# Fri3D_2026_Peripherals.net
KiCad netlist of a schematic drawn in Altium Designer
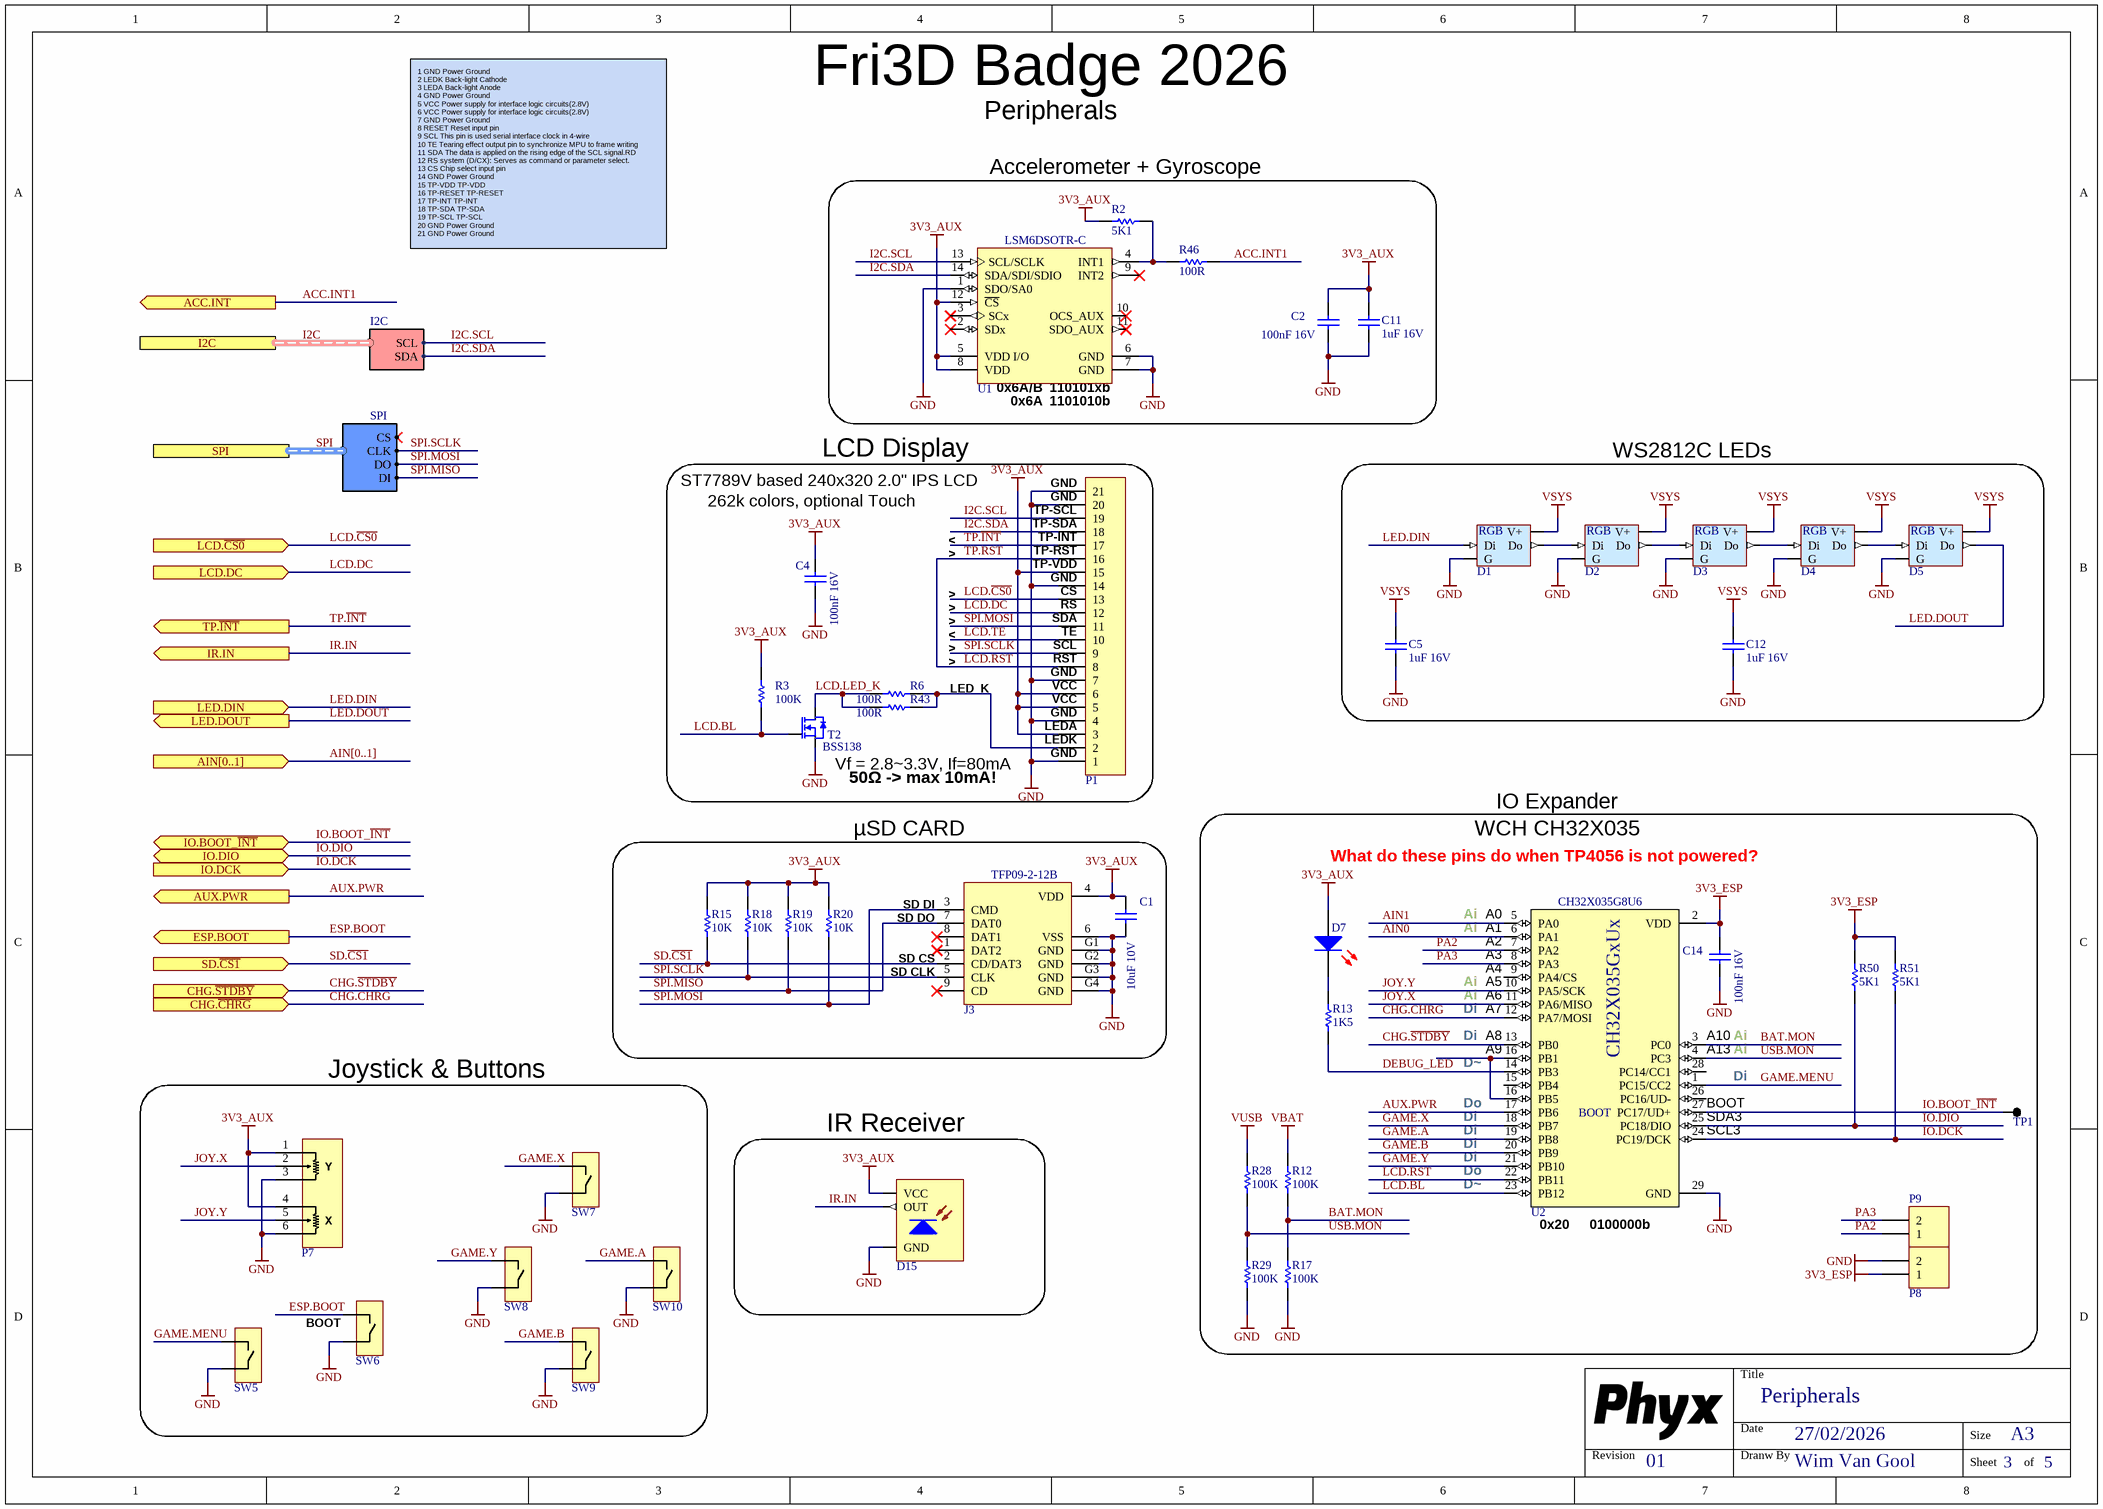
[diagram p0: Fri3D_2026_Peripherals.SchDoc]

(export (version "E")
  (design (tool "Eeschema 10.0.6"))
  (components
    (comp (ref "C1")
      (value "10uF 10V")
      (footprint "C0805_N")
      (description "Capacitor Ceramic")
      (libsource (lib "Phyx_Components") (part "CAP_CERAMIC"))
    )
    (comp (ref "C2")
      (value "100nF 16V")
      (footprint "C0603_N")
      (description "Capacitor Ceramic")
      (libsource (lib "Phyx_Components") (part "CAP_CERAMIC"))
    )
    (comp (ref "C4")
      (value "100nF 16V")
      (footprint "C0603_N")
      (description "Capacitor Ceramic")
      (libsource (lib "Phyx_Components") (part "CAP_CERAMIC"))
    )
    (comp (ref "C5")
      (value "1uF 16V")
      (footprint "C0603_N")
      (description "Capacitor Ceramic")
      (libsource (lib "Phyx_Components") (part "CAP_CERAMIC"))
    )
    (comp (ref "C11")
      (value "1uF 16V")
      (footprint "C0603_N")
      (description "Capacitor Ceramic")
      (libsource (lib "Phyx_Components") (part "CAP_CERAMIC"))
    )
    (comp (ref "C12")
      (value "1uF 16V")
      (footprint "C0603_N")
      (description "Capacitor Ceramic")
      (libsource (lib "Phyx_Components") (part "CAP_CERAMIC"))
    )
    (comp (ref "C14")
      (value "100nF 16V")
      (footprint "C0603_N")
      (description "Capacitor Ceramic")
      (libsource (lib "Phyx_Components") (part "CAP_CERAMIC"))
    )
    (comp (ref "D1")
      (value "WS2812 based digital RGB LED 5050 White package reduced current")
      (footprint "LED_5050_WS2812B_WHITE")
      (description "=Description")
      (libsource (lib "Phyx_Components") (part "LED_RGB_WS2812B_5050"))
    )
    (comp (ref "D2")
      (value "WS2812 based digital RGB LED 5050 White package reduced current")
      (footprint "LED_5050_WS2812B_WHITE")
      (description "=Description")
      (libsource (lib "Phyx_Components") (part "LED_RGB_WS2812B_5050"))
    )
    (comp (ref "D3")
      (value "WS2812 based digital RGB LED 5050 White package reduced current")
      (footprint "LED_5050_WS2812B_WHITE")
      (description "=Description")
      (libsource (lib "Phyx_Components") (part "LED_RGB_WS2812B_5050"))
    )
    (comp (ref "D4")
      (value "WS2812 based digital RGB LED 5050 White package reduced current")
      (footprint "LED_5050_WS2812B_WHITE")
      (description "=Description")
      (libsource (lib "Phyx_Components") (part "LED_RGB_WS2812B_5050"))
    )
    (comp (ref "D5")
      (value "WS2812 based digital RGB LED 5050 White package reduced current")
      (footprint "LED_5050_WS2812B_WHITE")
      (description "=Description")
      (libsource (lib "Phyx_Components") (part "LED_RGB_WS2812B_5050"))
    )
    (comp (ref "D7")
      (value "Default 0805 Red LED")
      (footprint "LED_0805_RD")
      (description "=Description")
      (libsource (lib "Phyx_Components") (part "LED_RED"))
    )
    (comp (ref "D15")
      (value "ZIRM-5042B-42-Z2 Infrared Receiver 38 kHz 45° 2.7-5.5V 940nm")
      (footprint "CHAU_ZIRM-5042B-42-Z2")
      (description "=Description")
      (libsource (lib "Phyx_Components") (part "PHO_IR_TSOP381x"))
    )
    (comp (ref "J3")
      (value "Micro SD PiPo Push-Push")
      (footprint "TFP09-2-12B")
      (description "=Description")
      (fields (field (name "SUPPLIER PART NUMBER 1") "TFP09-2-12B"))
      (libsource (lib "Phyx_Components") (part "TFP09-2-12B"))
    )
    (comp (ref "P1")
      (value "FH35C-21S-0.3SHW Top and Bottom Contacts 0.3mm 21pin")
      (footprint "HRS_FH35C-21S-0.3SHW")
      (libsource (lib "Phyx_Components") (part "Header 21"))
    )
    (comp (ref "P7")
      (value "PSP Mini Joystick")
      (footprint "PSP_Mini_Joystick")
      (libsource (lib "Phyx_Components") (part "PSP_Mini_Joystick"))
    )
    (comp (ref "P8")
      (value "Header 2")
      (footprint "HDR1X2")
      (libsource (lib "Phyx_Components") (part "Header 2"))
    )
    (comp (ref "P9")
      (value "Header 2")
      (footprint "HDR1X2")
      (libsource (lib "Phyx_Components") (part "Header 2"))
    )
    (comp (ref "R2")
      (value "5K1")
      (footprint "R0603_N")
      (libsource (lib "Phyx_Components") (part "RESISTOR"))
    )
    (comp (ref "R3")
      (value "100K")
      (footprint "R0603_N")
      (libsource (lib "Phyx_Components") (part "RESISTOR"))
    )
    (comp (ref "R6")
      (value "100R")
      (footprint "R0603_N")
      (libsource (lib "Phyx_Components") (part "RESISTOR"))
    )
    (comp (ref "R12")
      (value "100K")
      (footprint "R0603_N")
      (libsource (lib "Phyx_Components") (part "RESISTOR"))
    )
    (comp (ref "R13")
      (value "1K5")
      (footprint "R0603_N")
      (libsource (lib "Phyx_Components") (part "RESISTOR"))
    )
    (comp (ref "R15")
      (value "10K")
      (footprint "R0603_N")
      (libsource (lib "Phyx_Components") (part "RESISTOR"))
    )
    (comp (ref "R17")
      (value "100K")
      (footprint "R0603_N")
      (libsource (lib "Phyx_Components") (part "RESISTOR"))
    )
    (comp (ref "R18")
      (value "10K")
      (footprint "R0603_N")
      (libsource (lib "Phyx_Components") (part "RESISTOR"))
    )
    (comp (ref "R19")
      (value "10K")
      (footprint "R0603_N")
      (libsource (lib "Phyx_Components") (part "RESISTOR"))
    )
    (comp (ref "R20")
      (value "10K")
      (footprint "R0603_N")
      (libsource (lib "Phyx_Components") (part "RESISTOR"))
    )
    (comp (ref "R28")
      (value "100K")
      (footprint "R0603_N")
      (libsource (lib "Phyx_Components") (part "RESISTOR"))
    )
    (comp (ref "R29")
      (value "100K")
      (footprint "R0603_N")
      (libsource (lib "Phyx_Components") (part "RESISTOR"))
    )
    (comp (ref "R43")
      (value "100R")
      (footprint "R0603_N")
      (libsource (lib "Phyx_Components") (part "RESISTOR"))
    )
    (comp (ref "R46")
      (value "100R")
      (footprint "R0603_N")
      (libsource (lib "Phyx_Components") (part "RESISTOR"))
    )
    (comp (ref "R50")
      (value "5K1")
      (footprint "R0603_N")
      (libsource (lib "Phyx_Components") (part "RESISTOR"))
    )
    (comp (ref "R51")
      (value "5K1")
      (footprint "R0603_N")
      (libsource (lib "Phyx_Components") (part "RESISTOR"))
    )
    (comp (ref "SW5")
      (value "SKPMAME010 6x6 TACTG Switch")
      (footprint "ALPS_SKPMAME010")
      (libsource (lib "Phyx_Components") (part "SW_TACT"))
    )
    (comp (ref "SW6")
      (value "SKPMAME010 6x6 TACTG Switch")
      (footprint "ALPS_SKPMAME010")
      (libsource (lib "Phyx_Components") (part "SW_TACT"))
    )
    (comp (ref "SW7")
      (value "SKPMAME010 6x6 TACTG Switch")
      (footprint "ALPS_SKPMAME010")
      (libsource (lib "Phyx_Components") (part "SW_TACT"))
    )
    (comp (ref "SW8")
      (value "SKPMAME010 6x6 TACTG Switch")
      (footprint "ALPS_SKPMAME010")
      (libsource (lib "Phyx_Components") (part "SW_TACT"))
    )
    (comp (ref "SW9")
      (value "SKPMAME010 6x6 TACTG Switch")
      (footprint "ALPS_SKPMAME010")
      (libsource (lib "Phyx_Components") (part "SW_TACT"))
    )
    (comp (ref "SW10")
      (value "SKPMAME010 6x6 TACTG Switch")
      (footprint "ALPS_SKPMAME010")
      (libsource (lib "Phyx_Components") (part "SW_TACT"))
    )
    (comp (ref "T2")
      (value "BSS138")
      (footprint "SOT23-3")
      (fields (field (name "Comment") "0.2A N-Ch MOSFET Vgs 3.2"))
      (libsource (lib "Phyx_Components") (part "N_MOSFET_GSD"))
    )
    (comp (ref "TP1")
      (value "TEST_PAD")
      (footprint "TP_1.5mm_0.9mm")
      (libsource (lib "Phyx_Components") (part "TEST_PAD"))
    )
    (comp (ref "U1")
      (value "LSM6DSOTR-C")
      (footprint "STM_LGA14_2.5x3")
      (description "ACCELERO GYRO # LSM6DSOTR-C")
      (fields (field (name "Comment") "Acceleration ±2, ±4, ±8, ±16g Gyro ±125, ±250, ±500, ±1000, ±2000dps"))
      (libsource (lib "Phyx_Components") (part "STM_LSM6DSO"))
    )
    (comp (ref "U2")
      (value "CH32X035G8U6")
      (footprint "QFN_28_4.0x4.0_P0.4")
      (fields
        (field (name "Comment") "WCH CH32X035G8U6 QFN28 RISC-V 32-bit MCU, 62KB Flash, 10KB RAM, USB PD")
      )
      (libsource (lib "Phyx_Components") (part "WCH_CH32X035GxUx"))
    )
  )
  (nets
    (net (code "3") (name "/ACC.INT1") (class "Default")
      (node (ref "R46") (pin "2") (pinfunction "2_2") (pintype "passive"))
    )
    (net (code "4") (name "/AIN0") (class "Default")
      (node (ref "U2") (pin "6") (pinfunction "PA1_6") (pintype "bidirectional"))
    )
    (net (code "5") (name "/AIN1") (class "Default")
      (node (ref "U2") (pin "5") (pinfunction "PA0_5") (pintype "bidirectional"))
    )
    (net (code "7") (name "/AUX.PWR") (class "Default")
      (node (ref "U2") (pin "17") (pinfunction "PB6_17") (pintype "bidirectional"))
    )
    (net (code "8") (name "/BAT.MON") (class "Default")
      (node (ref "R12") (pin "2") (pinfunction "2_2") (pintype "passive"))
      (node (ref "R17") (pin "1") (pinfunction "1_1") (pintype "passive"))
      (node (ref "U2") (pin "3") (pinfunction "PC0_3") (pintype "bidirectional"))
    )
    (net (code "9") (name "/CHG.~{CHRG}") (class "Default")
      (node (ref "U2") (pin "12") (pinfunction "PA7/MOSI_12") (pintype "bidirectional"))
    )
    (net (code "10") (name "/CHG.~{STDBY}") (class "Default")
      (node (ref "U2") (pin "13") (pinfunction "PB0_13") (pintype "bidirectional"))
    )
    (net (code "11") (name "/DEBUG_LED") (class "Default")
      (node (ref "R13") (pin "2") (pinfunction "2_2") (pintype "passive"))
      (node (ref "U2") (pin "14") (pinfunction "PB3_14") (pintype "bidirectional"))
    )
    (net (code "12") (name "/ESP.BOOT") (class "Default")
      (node (ref "SW6") (pin "1") (pinfunction "1_1") (pintype "passive"))
    )
    (net (code "13") (name "/GAME.A") (class "Default")
      (node (ref "SW10") (pin "1") (pinfunction "1_1") (pintype "passive"))
      (node (ref "U2") (pin "19") (pinfunction "PB8_19") (pintype "bidirectional"))
    )
    (net (code "14") (name "/GAME.B") (class "Default")
      (node (ref "SW9") (pin "1") (pinfunction "1_1") (pintype "passive"))
      (node (ref "U2") (pin "20") (pinfunction "PB9_20") (pintype "bidirectional"))
    )
    (net (code "15") (name "/GAME.MENU") (class "Default")
      (node (ref "SW5") (pin "1") (pinfunction "1_1") (pintype "passive"))
      (node (ref "U2") (pin "1") (pinfunction "PC15/CC2_1") (pintype "bidirectional"))
    )
    (net (code "16") (name "/GAME.X") (class "Default")
      (node (ref "SW7") (pin "1") (pinfunction "1_1") (pintype "passive"))
      (node (ref "U2") (pin "18") (pinfunction "PB7_18") (pintype "bidirectional"))
    )
    (net (code "17") (name "/GAME.Y") (class "Default")
      (node (ref "SW8") (pin "1") (pinfunction "1_1") (pintype "passive"))
      (node (ref "U2") (pin "21") (pinfunction "PB10_21") (pintype "bidirectional"))
    )
    (net (code "18") (name "/I2C.SCL") (class "Default")
      (node (ref "P1") (pin "19") (pinfunction "19_19") (pintype "passive"))
      (node (ref "U1") (pin "13") (pinfunction "SCL/SCLK_13") (pintype "input"))
    )
    (net (code "19") (name "/I2C.SDA") (class "Default")
      (node (ref "P1") (pin "18") (pinfunction "18_18") (pintype "passive"))
      (node (ref "U1") (pin "14") (pinfunction "SDA/SDI/SDIO_14") (pintype "bidirectional"))
    )
    (net (code "21") (name "/IO.BOOT_~{INT}") (class "Default")
      (node (ref "TP1") (pin "1") (pinfunction "1_1") (pintype "passive"))
      (node (ref "U2") (pin "27") (pinfunction "PC17/UD+_27") (pintype "bidirectional"))
    )
    (net (code "22") (name "/IO.DCK") (class "Default")
      (node (ref "R51") (pin "2") (pinfunction "2_2") (pintype "passive"))
      (node (ref "U2") (pin "24") (pinfunction "PC19/DCK_24") (pintype "bidirectional"))
    )
    (net (code "23") (name "/IO.DIO") (class "Default")
      (node (ref "R50") (pin "2") (pinfunction "2_2") (pintype "passive"))
      (node (ref "U2") (pin "25") (pinfunction "PC18/DIO_25") (pintype "bidirectional"))
    )
    (net (code "24") (name "/IR.IN") (class "Default")
      (node (ref "D15") (pin "1") (pinfunction "OUT_1") (pintype "output"))
    )
    (net (code "25") (name "/JOY.X") (class "Default")
      (node (ref "P7") (pin "2") (pinfunction "2_2") (pintype "passive"))
      (node (ref "U2") (pin "11") (pinfunction "PA6/MISO_11") (pintype "bidirectional"))
    )
    (net (code "26") (name "/JOY.Y") (class "Default")
      (node (ref "P7") (pin "5") (pinfunction "5_5") (pintype "passive"))
      (node (ref "U2") (pin "10") (pinfunction "PA5/SCK_10") (pintype "bidirectional"))
    )
    (net (code "27") (name "/LCD.BL") (class "Default")
      (node (ref "R3") (pin "2") (pinfunction "2_2") (pintype "passive"))
      (node (ref "T2") (pin "1") (pinfunction "G_1") (pintype "passive"))
      (node (ref "U2") (pin "23") (pinfunction "PB12_23") (pintype "bidirectional"))
    )
    (net (code "28") (name "/LCD.DC") (class "Default")
      (node (ref "P1") (pin "12") (pinfunction "12_12") (pintype "passive"))
    )
    (net (code "29") (name "/LCD.LED_K") (class "Default")
      (node (ref "R43") (pin "2") (pinfunction "2_2") (pintype "passive"))
      (node (ref "R6") (pin "2") (pinfunction "2_2") (pintype "passive"))
      (node (ref "T2") (pin "3") (pinfunction "D_3") (pintype "passive"))
    )
    (net (code "30") (name "/LCD.TE") (class "Default")
      (node (ref "P1") (pin "10") (pinfunction "10_10") (pintype "passive"))
    )
    (net (code "31") (name "/LCD.~{CS0}") (class "Default")
      (node (ref "P1") (pin "13") (pinfunction "13_13") (pintype "passive"))
    )
    (net (code "32") (name "/LCD.~{RST}") (class "Default")
      (node (ref "P1") (pin "16") (pinfunction "16_16") (pintype "passive"))
      (node (ref "P1") (pin "8") (pinfunction "8_8") (pintype "passive"))
      (node (ref "U2") (pin "22") (pinfunction "PB11_22") (pintype "bidirectional"))
    )
    (net (code "33") (name "/LED.DIN") (class "Default")
      (node (ref "D1") (pin "4") (pinfunction "Di_4") (pintype "input"))
    )
    (net (code "34") (name "/LED.DOUT") (class "Default")
      (node (ref "D5") (pin "2") (pinfunction "Do_2") (pintype "output"))
    )
    (net (code "35") (name "/PA2") (class "Default")
      (node (ref "P9") (pin "1") (pinfunction "1_1") (pintype "passive"))
      (node (ref "U2") (pin "7") (pinfunction "PA2_7") (pintype "bidirectional"))
    )
    (net (code "36") (name "/PA3") (class "Default")
      (node (ref "P9") (pin "2") (pinfunction "2_2") (pintype "passive"))
      (node (ref "U2") (pin "8") (pinfunction "PA3_8") (pintype "bidirectional"))
    )
    (net (code "37") (name "/SD.~{CS1}") (class "Default")
      (node (ref "J3") (pin "2") (pinfunction "CD/DAT3_2") (pintype "passive"))
      (node (ref "R15") (pin "2") (pinfunction "2_2") (pintype "passive"))
    )
    (net (code "38") (name "/SPI.MISO") (class "Default")
      (node (ref "J3") (pin "7") (pinfunction "DAT0_7") (pintype "passive"))
      (node (ref "R19") (pin "2") (pinfunction "2_2") (pintype "passive"))
    )
    (net (code "39") (name "/SPI.MOSI") (class "Default")
      (node (ref "J3") (pin "3") (pinfunction "CMD_3") (pintype "passive"))
      (node (ref "P1") (pin "11") (pinfunction "11_11") (pintype "passive"))
      (node (ref "R20") (pin "2") (pinfunction "2_2") (pintype "passive"))
    )
    (net (code "40") (name "/SPI.SCLK") (class "Default")
      (node (ref "J3") (pin "5") (pinfunction "CLK_5") (pintype "passive"))
      (node (ref "P1") (pin "9") (pinfunction "9_9") (pintype "passive"))
      (node (ref "R18") (pin "2") (pinfunction "2_2") (pintype "passive"))
    )
    (net (code "42") (name "/TP.~{INT}") (class "Default")
      (node (ref "P1") (pin "17") (pinfunction "17_17") (pintype "passive"))
    )
    (net (code "43") (name "/USB.MON") (class "Default")
      (node (ref "R28") (pin "2") (pinfunction "2_2") (pintype "passive"))
      (node (ref "R29") (pin "1") (pinfunction "1_1") (pintype "passive"))
      (node (ref "U2") (pin "4") (pinfunction "PC3_4") (pintype "bidirectional"))
    )
    (net (code "44") (name "3V3_AUX") (class "Default")
      (node (ref "C1") (pin "1") (pinfunction "1_1") (pintype "passive"))
      (node (ref "C11") (pin "1") (pinfunction "1_1") (pintype "passive"))
      (node (ref "C2") (pin "1") (pinfunction "1_1") (pintype "passive"))
      (node (ref "C4") (pin "1") (pinfunction "1_1") (pintype "passive"))
      (node (ref "D15") (pin "3") (pinfunction "VCC_3") (pintype "power_in"))
      (node (ref "D7") (pin "1") (pinfunction "A_1") (pintype "passive"))
      (node (ref "J3") (pin "4") (pinfunction "VDD_4") (pintype "power_in"))
      (node (ref "P1") (pin "15") (pinfunction "15_15") (pintype "passive"))
      (node (ref "P1") (pin "3") (pinfunction "3_3") (pintype "passive"))
      (node (ref "P1") (pin "5") (pinfunction "5_5") (pintype "passive"))
      (node (ref "P1") (pin "6") (pinfunction "6_6") (pintype "passive"))
      (node (ref "P7") (pin "1") (pinfunction "1_1") (pintype "passive"))
      (node (ref "P7") (pin "4") (pinfunction "4_4") (pintype "passive"))
      (node (ref "R15") (pin "1") (pinfunction "1_1") (pintype "passive"))
      (node (ref "R18") (pin "1") (pinfunction "1_1") (pintype "passive"))
      (node (ref "R19") (pin "1") (pinfunction "1_1") (pintype "passive"))
      (node (ref "R2") (pin "1") (pinfunction "1_1") (pintype "passive"))
      (node (ref "R20") (pin "1") (pinfunction "1_1") (pintype "passive"))
      (node (ref "R3") (pin "1") (pinfunction "1_1") (pintype "passive"))
      (node (ref "U1") (pin "12") (pinfunction "~{CS}_12") (pintype "input"))
      (node (ref "U1") (pin "5") (pinfunction "VDD_I/O_5") (pintype "power_in"))
      (node (ref "U1") (pin "8") (pinfunction "VDD_8") (pintype "power_in"))
    )
    (net (code "45") (name "3V3_ESP") (class "Default")
      (node (ref "C14") (pin "1") (pinfunction "1_1") (pintype "passive"))
      (node (ref "P8") (pin "1") (pinfunction "1_1") (pintype "passive"))
      (node (ref "R50") (pin "1") (pinfunction "1_1") (pintype "passive"))
      (node (ref "R51") (pin "1") (pinfunction "1_1") (pintype "passive"))
      (node (ref "U2") (pin "2") (pinfunction "VDD_2") (pintype "power_in"))
    )
    (net (code "46") (name "GND") (class "Default")
      (node (ref "C1") (pin "2") (pinfunction "2_2") (pintype "passive"))
      (node (ref "C11") (pin "2") (pinfunction "2_2") (pintype "passive"))
      (node (ref "C12") (pin "2") (pinfunction "2_2") (pintype "passive"))
      (node (ref "C14") (pin "2") (pinfunction "2_2") (pintype "passive"))
      (node (ref "C2") (pin "2") (pinfunction "2_2") (pintype "passive"))
      (node (ref "C4") (pin "2") (pinfunction "2_2") (pintype "passive"))
      (node (ref "C5") (pin "2") (pinfunction "2_2") (pintype "passive"))
      (node (ref "D1") (pin "3") (pinfunction "G_3") (pintype "power_in"))
      (node (ref "D15") (pin "2") (pinfunction "GND_2") (pintype "power_in"))
      (node (ref "D2") (pin "3") (pinfunction "G_3") (pintype "power_in"))
      (node (ref "D3") (pin "3") (pinfunction "G_3") (pintype "power_in"))
      (node (ref "D4") (pin "3") (pinfunction "G_3") (pintype "power_in"))
      (node (ref "D5") (pin "3") (pinfunction "G_3") (pintype "power_in"))
      (node (ref "J3") (pin "6") (pinfunction "VSS_6") (pintype "power_in"))
      (node (ref "J3") (pin "G1") (pinfunction "GND_G1") (pintype "power_in"))
      (node (ref "J3") (pin "G2") (pinfunction "GND_G2") (pintype "power_in"))
      (node (ref "J3") (pin "G3") (pinfunction "GND_G3") (pintype "power_in"))
      (node (ref "J3") (pin "G4") (pinfunction "GND_G4") (pintype "power_in"))
      (node (ref "P1") (pin "1") (pinfunction "1_1") (pintype "passive"))
      (node (ref "P1") (pin "14") (pinfunction "14_14") (pintype "passive"))
      (node (ref "P1") (pin "20") (pinfunction "20_20") (pintype "passive"))
      (node (ref "P1") (pin "21") (pinfunction "21_21") (pintype "passive"))
      (node (ref "P1") (pin "4") (pinfunction "4_4") (pintype "passive"))
      (node (ref "P1") (pin "7") (pinfunction "7_7") (pintype "passive"))
      (node (ref "P7") (pin "3") (pinfunction "3_3") (pintype "passive"))
      (node (ref "P7") (pin "6") (pinfunction "6_6") (pintype "passive"))
      (node (ref "P8") (pin "2") (pinfunction "2_2") (pintype "passive"))
      (node (ref "R17") (pin "2") (pinfunction "2_2") (pintype "passive"))
      (node (ref "R29") (pin "2") (pinfunction "2_2") (pintype "passive"))
      (node (ref "SW10") (pin "2") (pinfunction "2_2") (pintype "passive"))
      (node (ref "SW5") (pin "2") (pinfunction "2_2") (pintype "passive"))
      (node (ref "SW6") (pin "2") (pinfunction "2_2") (pintype "passive"))
      (node (ref "SW7") (pin "2") (pinfunction "2_2") (pintype "passive"))
      (node (ref "SW8") (pin "2") (pinfunction "2_2") (pintype "passive"))
      (node (ref "SW9") (pin "2") (pinfunction "2_2") (pintype "passive"))
      (node (ref "T2") (pin "2") (pinfunction "S_2") (pintype "passive"))
      (node (ref "U1") (pin "1") (pinfunction "SDO/SA0_1") (pintype "bidirectional"))
      (node (ref "U1") (pin "6") (pinfunction "GND_6") (pintype "power_in"))
      (node (ref "U1") (pin "7") (pinfunction "GND_7") (pintype "power_in"))
      (node (ref "U2") (pin "29") (pinfunction "GND_29") (pintype "power_in"))
    )
    (net (code "47") (name "Net-(D1-Do)") (class "Default")
      (node (ref "D1") (pin "2") (pinfunction "Do_2") (pintype "output"))
      (node (ref "D2") (pin "4") (pinfunction "Di_4") (pintype "input"))
    )
    (net (code "48") (name "Net-(D2-Do)") (class "Default")
      (node (ref "D2") (pin "2") (pinfunction "Do_2") (pintype "output"))
      (node (ref "D3") (pin "4") (pinfunction "Di_4") (pintype "input"))
    )
    (net (code "49") (name "Net-(D3-Do)") (class "Default")
      (node (ref "D3") (pin "2") (pinfunction "Do_2") (pintype "output"))
      (node (ref "D4") (pin "4") (pinfunction "Di_4") (pintype "input"))
    )
    (net (code "50") (name "Net-(D4-Do)") (class "Default")
      (node (ref "D4") (pin "2") (pinfunction "Do_2") (pintype "output"))
      (node (ref "D5") (pin "4") (pinfunction "Di_4") (pintype "input"))
    )
    (net (code "51") (name "Net-(D7-K)") (class "Default")
      (node (ref "D7") (pin "2") (pinfunction "K_2") (pintype "passive"))
      (node (ref "R13") (pin "1") (pinfunction "1_1") (pintype "passive"))
    )
    (net (code "52") (name "Net-(P1-Pad2)") (class "Default")
      (node (ref "P1") (pin "2") (pinfunction "2_2") (pintype "passive"))
      (node (ref "R43") (pin "1") (pinfunction "1_1") (pintype "passive"))
      (node (ref "R6") (pin "1") (pinfunction "1_1") (pintype "passive"))
    )
    (net (code "53") (name "Net-(U1-INT1)") (class "Default")
      (node (ref "R2") (pin "2") (pinfunction "2_2") (pintype "passive"))
      (node (ref "R46") (pin "1") (pinfunction "1_1") (pintype "passive"))
      (node (ref "U1") (pin "4") (pinfunction "INT1_4") (pintype "output"))
    )
    (net (code "54") (name "Net-(U2-PB1)") (class "Default")
      (node (ref "U2") (pin "16") (pinfunction "PB1_16") (pintype "bidirectional"))
    )
    (net (code "55") (name "VBAT") (class "Default")
      (node (ref "R12") (pin "1") (pinfunction "1_1") (pintype "passive"))
    )
    (net (code "56") (name "VSYS") (class "Default")
      (node (ref "C12") (pin "1") (pinfunction "1_1") (pintype "passive"))
      (node (ref "C5") (pin "1") (pinfunction "1_1") (pintype "passive"))
      (node (ref "D1") (pin "1") (pinfunction "V+_1") (pintype "power_in"))
      (node (ref "D2") (pin "1") (pinfunction "V+_1") (pintype "power_in"))
      (node (ref "D3") (pin "1") (pinfunction "V+_1") (pintype "power_in"))
      (node (ref "D4") (pin "1") (pinfunction "V+_1") (pintype "power_in"))
      (node (ref "D5") (pin "1") (pinfunction "V+_1") (pintype "power_in"))
    )
    (net (code "57") (name "VUSB") (class "Default")
      (node (ref "R28") (pin "1") (pinfunction "1_1") (pintype "passive"))
    )
    (net (code "58") (name "unconnected-(J3-CD-Pad9)") (class "Default")
      (node (ref "J3") (pin "9") (pinfunction "CD_9") (pintype "passive+no_connect"))
    )
    (net (code "59") (name "unconnected-(J3-DAT1-Pad8)") (class "Default")
      (node (ref "J3") (pin "8") (pinfunction "DAT1_8") (pintype "passive+no_connect"))
    )
    (net (code "60") (name "unconnected-(J3-DAT2-Pad1)") (class "Default")
      (node (ref "J3") (pin "1") (pinfunction "DAT2_1") (pintype "passive+no_connect"))
    )
    (net (code "61") (name "unconnected-(U1-INT2-Pad9)") (class "Default")
      (node (ref "U1") (pin "9") (pinfunction "INT2_9") (pintype "output+no_connect"))
    )
    (net (code "62") (name "unconnected-(U1-OCS_AUX-Pad10)") (class "Default")
      (node (ref "U1") (pin "10") (pinfunction "OCS_AUX_10") (pintype "passive+no_connect"))
    )
    (net (code "63") (name "unconnected-(U1-SCx-Pad3)") (class "Default")
      (node (ref "U1") (pin "3") (pinfunction "SCx_3") (pintype "output+no_connect"))
    )
    (net (code "64") (name "unconnected-(U1-SDO_AUX-Pad11)") (class "Default")
      (node (ref "U1") (pin "11") (pinfunction "SDO_AUX_11") (pintype "output+no_connect"))
    )
    (net (code "65") (name "unconnected-(U1-SDx-Pad2)") (class "Default")
      (node (ref "U1") (pin "2") (pinfunction "SDx_2") (pintype "bidirectional+no_connect"))
    )
    (net (code "66") (name "unconnected-(U2-PA4{slash}CS-Pad9)") (class "Default")
      (node (ref "U2") (pin "9") (pinfunction "PA4/CS_9") (pintype "bidirectional"))
    )
    (net (code "67") (name "unconnected-(U2-PB4-Pad15)") (class "Default")
      (node (ref "U2") (pin "15") (pinfunction "PB4_15") (pintype "bidirectional"))
    )
    (net (code "68") (name "unconnected-(U2-PC14{slash}CC1-Pad28)") (class "Default")
      (node (ref "U2") (pin "28") (pinfunction "PC14/CC1_28") (pintype "bidirectional"))
    )
    (net (code "69") (name "unconnected-(U2-PC16{slash}UD--Pad26)") (class "Default")
      (node (ref "U2") (pin "26") (pinfunction "PC16/UD-_26") (pintype "bidirectional"))
    )
  )
)
